# I2C_Network.net
KiCad netlist of a schematic drawn in Altium Designer
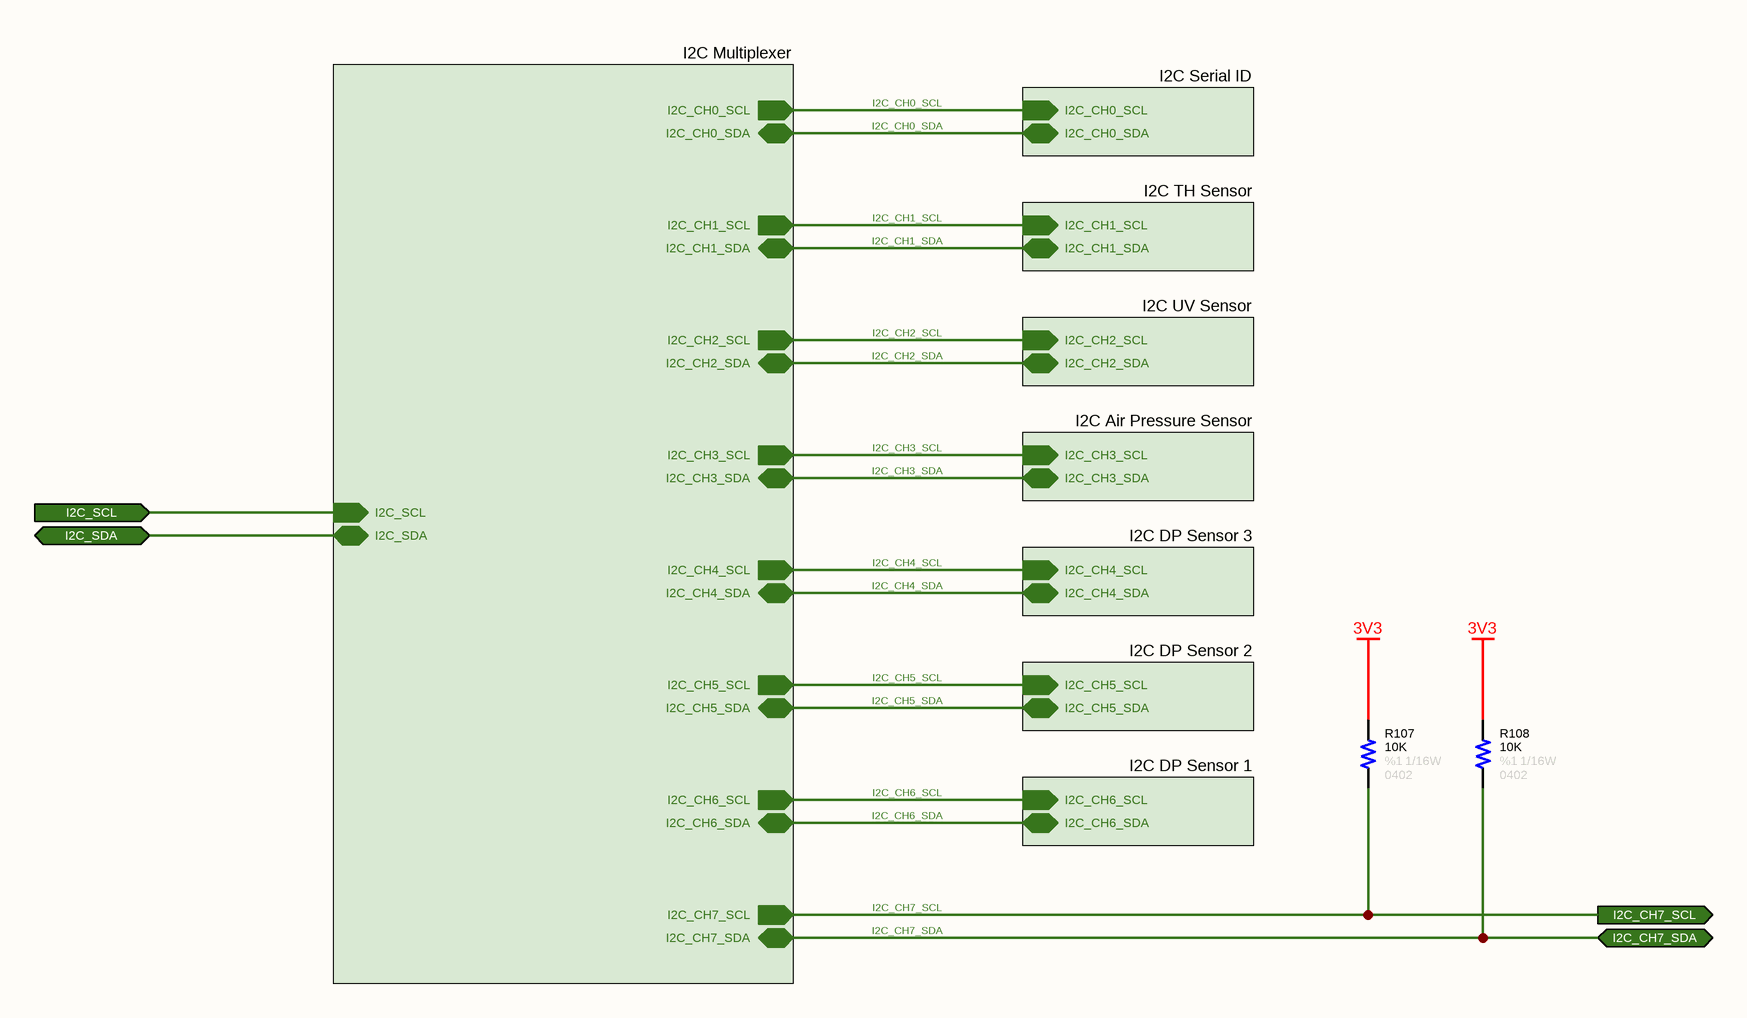
[diagram p0: I2C Network.SchDoc]

(export (version "E")
  (design (tool "Eeschema 10.0.6"))
  (components
    (comp (ref "R107")
      (value "10K")
      (footprint "RESISTOR_0402")
      (description "Thick Film Resistors - SMD 1/16 W 10 KOhm 1%")
      (fields
        (field (name "MANUFACTURER PART NUMBER") "CRCW040210K0FKED")
        (field (name "TOLERANCE") "%1")
        (field (name "CASE") "0402")
        (field (name "POWER") "1/16W")
        (field (name "Comment") "10K - 0402 - %1 - 1/16W")
      )
      (libsource (lib "Akkoyun") (part "Resistor - 10K [0402]"))
    )
    (comp (ref "R108")
      (value "10K")
      (footprint "RESISTOR_0402")
      (description "Thick Film Resistors - SMD 1/16 W 10 KOhm 1%")
      (fields
        (field (name "MANUFACTURER PART NUMBER") "CRCW040210K0FKED")
        (field (name "TOLERANCE") "%1")
        (field (name "CASE") "0402")
        (field (name "POWER") "1/16W")
        (field (name "Comment") "10K - 0402 - %1 - 1/16W")
      )
      (libsource (lib "Akkoyun") (part "Resistor - 10K [0402]"))
    )
  )
  (nets
    (net (code "15") (name "/I2C_CH7_SCL") (class "Default")
      (node (ref "R107") (pin "1") (pinfunction "1_1") (pintype "passive"))
    )
    (net (code "16") (name "/I2C_CH7_SDA") (class "Default")
      (node (ref "R108") (pin "1") (pinfunction "1_1") (pintype "passive"))
    )
    (net (code "19") (name "3V3") (class "Default")
      (node (ref "R107") (pin "2") (pinfunction "2_2") (pintype "passive"))
      (node (ref "R108") (pin "2") (pinfunction "2_2") (pintype "passive"))
    )
  )
)
